# Sheet5.net
KiCad netlist of a schematic drawn in Altium Designer
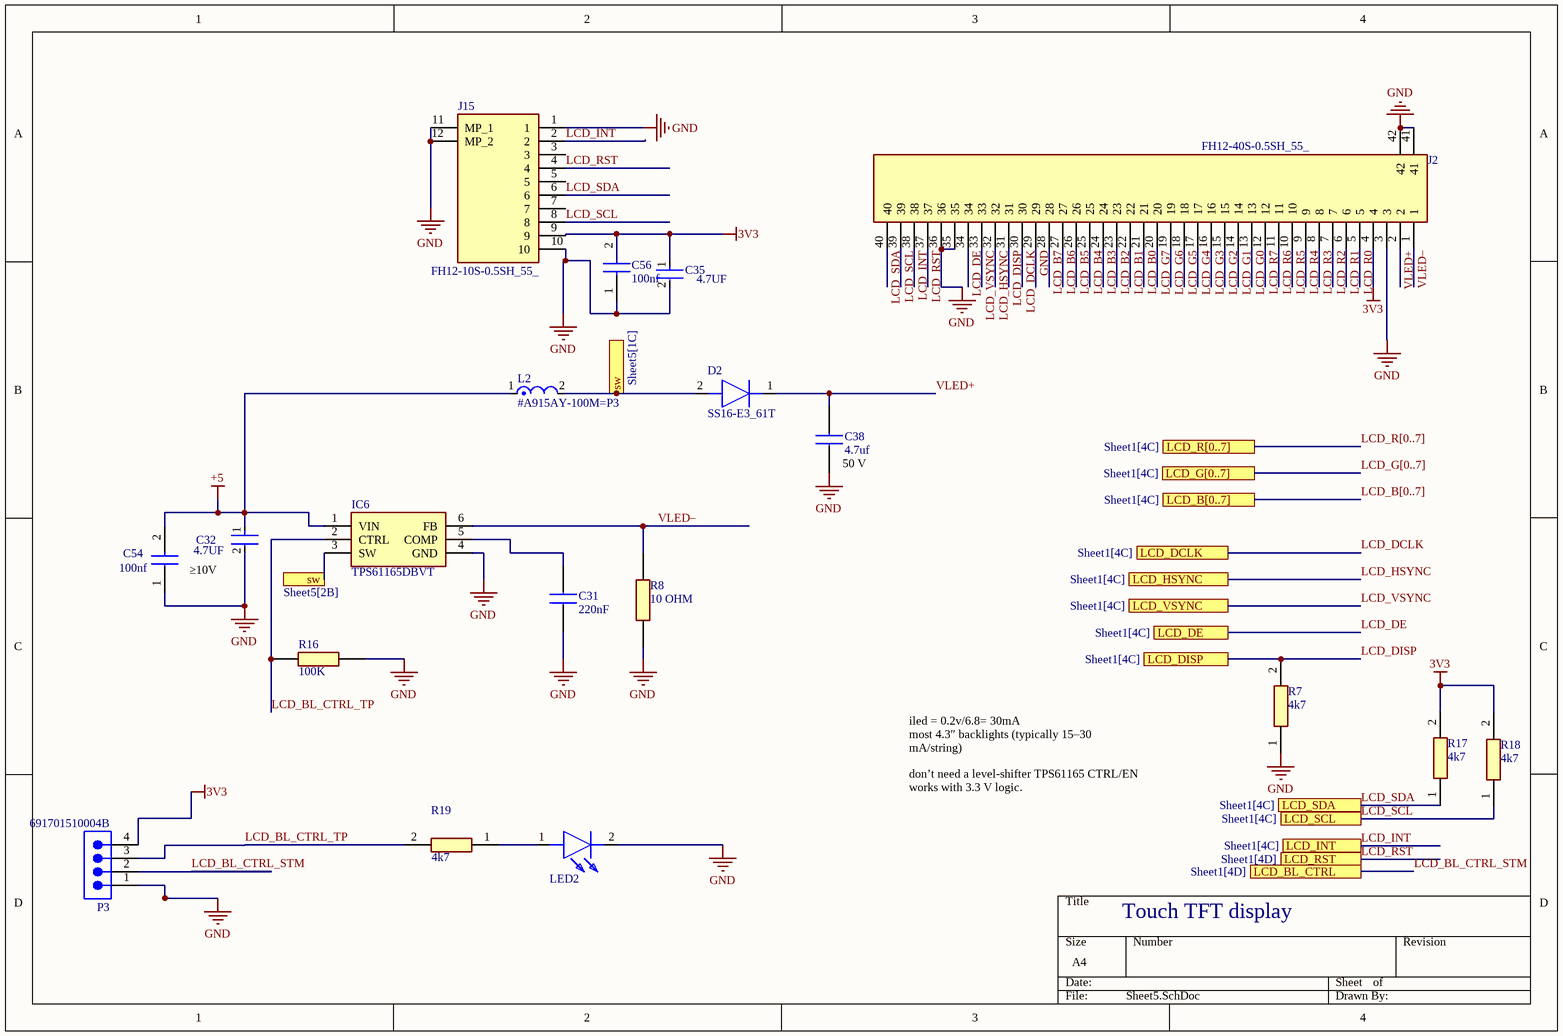
[diagram p0: Sheet5.SchDoc]

(export (version "E")
  (design (tool "Eeschema 10.0.6"))
  (components
    (comp (ref "C31")
      (value "220nF")
      (footprint "CAPC1608X87N")
      (description "WALSIN - 0603B223K500CT - CAPACITOR, MLCC, X7R, 0.022UF, 50V, 0603")
      (fields
        (field (name "MANUFACTURER_PART_NUMBER") "0603B223K500CT")
        (field (name "MOUSER PART NUMBER") "791-0603B223K500CT")
      )
      (libsource (lib "0603B223K500CT") (part "0603B223K500CT"))
    )
    (comp (ref "C32")
      (value "4.7UF")
      (footprint "FP-CL10-IPC_A")
      (description "Cap Ceramic 2.2uF 10V X7R ±10% Pad SMD 0603 +125°C T/R")
      (fields (field (name "TOLERANCE") "10%"))
      (libsource (lib "Altium Content Vault") (part "b4654b650e69147ec39a6b967a45e02"))
    )
    (comp (ref "C35")
      (value "4.7UF")
      (footprint "FP-CL10-IPC_A")
      (description "Cap Ceramic 2.2uF 10V X7R ±10% Pad SMD 0603 +125°C T/R")
      (fields (field (name "TOLERANCE") "10%"))
      (libsource (lib "Altium Content Vault") (part "b4654b650e69147ec39a6b967a45e02"))
    )
    (comp (ref "C38")
      (value "4.7uf")
      (footprint "CAPC1608X95N")
      (fields (field (name "MANUFACTURER_PART_NUMBER") "0603X105K250CT"))
      (libsource (lib "0603X105K250CT") (part "0603X105K250CT"))
    )
    (comp (ref "C54")
      (value "100nf")
      (footprint "SamacSys:CAPC1608X95N")
      (description "Capacitor")
      (fields (field (name "MANUFACTURER_PART_NUMBER") "VJ0603Y104KXACW1BC"))
      (libsource (lib "*") (part "VJ0603Y104KXACW1BC"))
    )
    (comp (ref "C56")
      (value "100nf")
      (footprint "SamacSys:CAPC1608X95N")
      (description "Capacitor")
      (fields (field (name "MANUFACTURER_PART_NUMBER") "VJ0603Y104KXACW1BC"))
      (libsource (lib "*") (part "VJ0603Y104KXACW1BC"))
    )
    (comp (ref "D2")
      (value "SS16-E3_61T")
      (footprint "SamacSys:DIOM5127X229N")
      (description "Diode")
      (fields
        (field (name "MANUFACTURER_PART_NUMBER") "SS16-E3/61T")
        (field (name "MOUSER PART NUMBER") "625-SS16-E3")
      )
      (libsource (lib "*") (part "SS16-E3_61T"))
    )
    (comp (ref "IC6")
      (value "TPS61165DBVT")
      (footprint "SamacSys:SOT95P280X145-6N")
      (description "Integrated Circuit")
      (fields (field (name "MOUSER PART NUMBER") "595-TPS61165DBVT"))
      (libsource (lib "*") (part "TPS61165DBVT"))
    )
    (comp (ref "J2")
      (value "FH12-40S-0.5SH_55_")
      (footprint "SamacSys:FH1240S05SH55")
      (description "Connector")
      (fields
        (field (name "MANUFACTURER_PART_NUMBER") "FH12-40S-0.5SH(55)")
        (field (name "MOUSER PART NUMBER") "798-FH12-40S-0.5SH55")
      )
      (libsource (lib "*") (part "FH12-40S-0.5SH_55_"))
    )
    (comp (ref "J15")
      (value "FH12-10S-0.5SH_55_")
      (footprint "SamacSys:FH1210S05SH55")
      (description "Connector")
      (fields
        (field (name "MANUFACTURER_PART_NUMBER") "FH12-10S-0.5SH(55)")
        (field (name "MOUSER PART NUMBER") "798-FH12-10S-0.5SH55")
      )
      (libsource (lib "*") (part "FH12-10S-0.5SH_55_"))
    )
    (comp (ref "L2")
      (value "#A915AY-100M=P3")
      (footprint "FP-D53LC-MFG")
      (description "FIXED IND 10UH 1.49A 90 MOHM SMD")
      (fields (field (name "TOLERANCE") "20%"))
      (libsource (lib "Altium Content Vault") (part "ae3b6ca10b736fc74204ce580bf9b8e"))
    )
    (comp (ref "LED2")
      (value "KPTL-3216SURCK-01-VS")
      (footprint "SamacSys:KPTL3216SURCK01VS")
      (description "LED")
      (libsource (lib "*") (part "KPTL-3216SURCK-01-VS"))
    )
    (comp (ref "P3")
      (value "691701510004B")
      (footprint "691701510004B")
      (description "Terminal Block, 5.08MM, Close Vertical Pcb Header, Thr Type, 4 Pins")
      (libsource (lib "Altium Content Vault") (part "TBL - 1R - 04P - Male"))
    )
    (comp (ref "R7")
      (value "4k7")
      (footprint "SamacSys:RESC1608X55N")
      (description "Resistor")
      (fields
        (field (name "MANUFACTURER_PART_NUMBER") "CRCW06034K70JNEAC")
        (field (name "MOUSER PART NUMBER") "71-CRCW06034K70JNEAC")
      )
      (libsource (lib "*") (part "CRCW06034K70JNEAC"))
    )
    (comp (ref "R8")
      (value "10 OHM")
      (footprint "RESC1608X50N")
      (description "AR03BTCX6R80")
      (fields
        (field (name "MANUFACTURER_PART_NUMBER") "RCA0603100KFKEA")
        (field (name "MOUSER PART NUMBER") "71-RCA0603100KFKEA")
      )
      (libsource (lib "RCA0603100KFKEA") (part "RCA0603100KFKEA"))
    )
    (comp (ref "R16")
      (value "100K")
      (footprint "RESC1608X50N")
      (fields
        (field (name "MANUFACTURER_PART_NUMBER") "RCA0603100KFKEA")
        (field (name "MOUSER PART NUMBER") "71-RCA0603100KFKEA")
      )
      (libsource (lib "") (part "RCA0603100KFKEA_1"))
    )
    (comp (ref "R17")
      (value "4k7")
      (footprint "SamacSys:RESC1608X55N")
      (description "Resistor")
      (fields
        (field (name "MANUFACTURER_PART_NUMBER") "CRCW06034K70JNEAC")
        (field (name "MOUSER PART NUMBER") "71-CRCW06034K70JNEAC")
      )
      (libsource (lib "*") (part "CRCW06034K70JNEAC"))
    )
    (comp (ref "R18")
      (value "4k7")
      (footprint "SamacSys:RESC1608X55N")
      (description "Resistor")
      (fields
        (field (name "MANUFACTURER_PART_NUMBER") "CRCW06034K70JNEAC")
        (field (name "MOUSER PART NUMBER") "71-CRCW06034K70JNEAC")
      )
      (libsource (lib "*") (part "CRCW06034K70JNEAC"))
    )
    (comp (ref "R19")
      (value "4k7")
      (footprint "SamacSys:RESC1608X55N")
      (description "Resistor")
      (fields
        (field (name "MANUFACTURER_PART_NUMBER") "CRCW06034K70JNEAC")
        (field (name "MOUSER PART NUMBER") "71-CRCW06034K70JNEAC")
      )
      (libsource (lib "") (part "CRCW06034K70JNEAC_1"))
    )
  )
  (nets
    (net (code "1") (name "+5") (class "Default")
      (node (ref "C32") (pin "1") (pinfunction "1_1") (pintype "passive"))
      (node (ref "C54") (pin "2") (pinfunction "2_2") (pintype "passive"))
      (node (ref "IC6") (pin "1") (pinfunction "VIN_1") (pintype "passive"))
      (node (ref "L2") (pin "1") (pinfunction "1_1") (pintype "passive"))
    )
    (net (code "2") (name "/LCD_B0") (class "Default")
      (node (ref "J2") (pin "21") (pinfunction "21_21") (pintype "passive"))
    )
    (net (code "3") (name "/LCD_B1") (class "Default")
      (node (ref "J2") (pin "22") (pinfunction "22_22") (pintype "passive"))
    )
    (net (code "4") (name "/LCD_B2") (class "Default")
      (node (ref "J2") (pin "23") (pinfunction "23_23") (pintype "passive"))
    )
    (net (code "5") (name "/LCD_B3") (class "Default")
      (node (ref "J2") (pin "24") (pinfunction "24_24") (pintype "passive"))
    )
    (net (code "6") (name "/LCD_B4") (class "Default")
      (node (ref "J2") (pin "25") (pinfunction "25_25") (pintype "passive"))
    )
    (net (code "7") (name "/LCD_B5") (class "Default")
      (node (ref "J2") (pin "26") (pinfunction "26_26") (pintype "passive"))
    )
    (net (code "8") (name "/LCD_B6") (class "Default")
      (node (ref "J2") (pin "27") (pinfunction "27_27") (pintype "passive"))
    )
    (net (code "9") (name "/LCD_B7") (class "Default")
      (node (ref "J2") (pin "28") (pinfunction "28_28") (pintype "passive"))
    )
    (net (code "10") (name "/LCD_BL_CTRL_STM") (class "Default")
      (node (ref "P3") (pin "2") (pinfunction "2_2") (pintype "passive"))
    )
    (net (code "11") (name "/LCD_BL_CTRL_TP") (class "Default")
      (node (ref "IC6") (pin "2") (pinfunction "CTRL_2") (pintype "passive"))
      (node (ref "P3") (pin "3") (pinfunction "3_3") (pintype "passive"))
      (node (ref "R16") (pin "1") (pinfunction "1_1") (pintype "passive"))
      (node (ref "R19") (pin "2") (pinfunction "2_2") (pintype "passive"))
    )
    (net (code "13") (name "/LCD_DCLK") (class "Default")
      (node (ref "J2") (pin "30") (pinfunction "30_30") (pintype "passive"))
    )
    (net (code "14") (name "/LCD_DE") (class "Default")
      (node (ref "J2") (pin "34") (pinfunction "34_34") (pintype "passive"))
    )
    (net (code "15") (name "/LCD_DISP") (class "Default")
      (node (ref "J2") (pin "31") (pinfunction "31_31") (pintype "passive"))
      (node (ref "R7") (pin "2") (pinfunction "2_2") (pintype "passive"))
    )
    (net (code "16") (name "/LCD_G0") (class "Default")
      (node (ref "J2") (pin "13") (pinfunction "13_13") (pintype "passive"))
    )
    (net (code "17") (name "/LCD_G1") (class "Default")
      (node (ref "J2") (pin "14") (pinfunction "14_14") (pintype "passive"))
    )
    (net (code "18") (name "/LCD_G2") (class "Default")
      (node (ref "J2") (pin "15") (pinfunction "15_15") (pintype "passive"))
    )
    (net (code "19") (name "/LCD_G3") (class "Default")
      (node (ref "J2") (pin "16") (pinfunction "16_16") (pintype "passive"))
    )
    (net (code "20") (name "/LCD_G4") (class "Default")
      (node (ref "J2") (pin "17") (pinfunction "17_17") (pintype "passive"))
    )
    (net (code "21") (name "/LCD_G5") (class "Default")
      (node (ref "J2") (pin "18") (pinfunction "18_18") (pintype "passive"))
    )
    (net (code "22") (name "/LCD_G6") (class "Default")
      (node (ref "J2") (pin "19") (pinfunction "19_19") (pintype "passive"))
    )
    (net (code "23") (name "/LCD_G7") (class "Default")
      (node (ref "J2") (pin "20") (pinfunction "20_20") (pintype "passive"))
    )
    (net (code "25") (name "/LCD_HSYNC") (class "Default")
      (node (ref "J2") (pin "32") (pinfunction "32_32") (pintype "passive"))
    )
    (net (code "26") (name "/LCD_INT") (class "Default")
      (node (ref "J15") (pin "2") (pinfunction "2_2") (pintype "passive"))
      (node (ref "J2") (pin "38") (pinfunction "38_38") (pintype "passive"))
    )
    (net (code "27") (name "/LCD_R0") (class "Default")
      (node (ref "J2") (pin "5") (pinfunction "5_5") (pintype "passive"))
    )
    (net (code "28") (name "/LCD_R1") (class "Default")
      (node (ref "J2") (pin "6") (pinfunction "6_6") (pintype "passive"))
    )
    (net (code "29") (name "/LCD_R2") (class "Default")
      (node (ref "J2") (pin "7") (pinfunction "7_7") (pintype "passive"))
    )
    (net (code "30") (name "/LCD_R3") (class "Default")
      (node (ref "J2") (pin "8") (pinfunction "8_8") (pintype "passive"))
    )
    (net (code "31") (name "/LCD_R4") (class "Default")
      (node (ref "J2") (pin "9") (pinfunction "9_9") (pintype "passive"))
    )
    (net (code "32") (name "/LCD_R5") (class "Default")
      (node (ref "J2") (pin "10") (pinfunction "10_10") (pintype "passive"))
    )
    (net (code "33") (name "/LCD_R6") (class "Default")
      (node (ref "J2") (pin "11") (pinfunction "11_11") (pintype "passive"))
    )
    (net (code "34") (name "/LCD_R7") (class "Default")
      (node (ref "J2") (pin "12") (pinfunction "12_12") (pintype "passive"))
    )
    (net (code "35") (name "/LCD_RST") (class "Default")
      (node (ref "J15") (pin "4") (pinfunction "4_4") (pintype "passive"))
      (node (ref "J2") (pin "37") (pinfunction "37_37") (pintype "passive"))
    )
    (net (code "37") (name "/LCD_SCL") (class "Default")
      (node (ref "J15") (pin "8") (pinfunction "8_8") (pintype "passive"))
      (node (ref "J2") (pin "39") (pinfunction "39_39") (pintype "passive"))
      (node (ref "R18") (pin "1") (pinfunction "1_1") (pintype "passive"))
    )
    (net (code "38") (name "/LCD_SDA") (class "Default")
      (node (ref "J15") (pin "6") (pinfunction "6_6") (pintype "passive"))
      (node (ref "J2") (pin "40") (pinfunction "40_40") (pintype "passive"))
      (node (ref "R17") (pin "1") (pinfunction "1_1") (pintype "passive"))
    )
    (net (code "39") (name "/LCD_VSYNC") (class "Default")
      (node (ref "J2") (pin "33") (pinfunction "33_33") (pintype "passive"))
    )
    (net (code "40") (name "/VLED+") (class "Default")
      (node (ref "C38") (pin "2") (pinfunction "2_2") (pintype "passive"))
      (node (ref "D2") (pin "1") (pinfunction "K_1") (pintype "passive"))
      (node (ref "J2") (pin "2") (pinfunction "2_2") (pintype "passive"))
    )
    (net (code "41") (name "/VLED–") (class "Default")
      (node (ref "IC6") (pin "6") (pinfunction "FB_6") (pintype "passive"))
      (node (ref "J2") (pin "1") (pinfunction "1_1") (pintype "passive"))
      (node (ref "R8") (pin "2") (pinfunction "2_2") (pintype "passive"))
    )
    (net (code "42") (name "/sw") (class "Default")
      (node (ref "D2") (pin "2") (pinfunction "A_2") (pintype "passive"))
      (node (ref "IC6") (pin "3") (pinfunction "SW_3") (pintype "passive"))
      (node (ref "L2") (pin "2") (pinfunction "2_2") (pintype "passive"))
    )
    (net (code "43") (name "3V3") (class "Default")
      (node (ref "C35") (pin "1") (pinfunction "1_1") (pintype "passive"))
      (node (ref "C56") (pin "2") (pinfunction "2_2") (pintype "passive"))
      (node (ref "J15") (pin "9") (pinfunction "9_9") (pintype "passive"))
      (node (ref "J2") (pin "4") (pinfunction "4_4") (pintype "passive"))
      (node (ref "P3") (pin "4") (pinfunction "4_4") (pintype "passive"))
      (node (ref "R17") (pin "2") (pinfunction "2_2") (pintype "passive"))
      (node (ref "R18") (pin "2") (pinfunction "2_2") (pintype "passive"))
    )
    (net (code "44") (name "GND") (class "Default")
      (node (ref "C31") (pin "1") (pinfunction "1_1") (pintype "passive"))
      (node (ref "C32") (pin "2") (pinfunction "2_2") (pintype "passive"))
      (node (ref "C35") (pin "2") (pinfunction "2_2") (pintype "passive"))
      (node (ref "C38") (pin "1") (pinfunction "1_1") (pintype "passive"))
      (node (ref "C54") (pin "1") (pinfunction "1_1") (pintype "passive"))
      (node (ref "C56") (pin "1") (pinfunction "1_1") (pintype "passive"))
      (node (ref "IC6") (pin "4") (pinfunction "GND_4") (pintype "passive"))
      (node (ref "J15") (pin "1") (pinfunction "1_1") (pintype "passive"))
      (node (ref "J15") (pin "10") (pinfunction "10_10") (pintype "passive"))
      (node (ref "J15") (pin "11") (pinfunction "MP_1_11") (pintype "passive"))
      (node (ref "J15") (pin "12") (pinfunction "MP_2_12") (pintype "passive"))
      (node (ref "J2") (pin "29") (pinfunction "29_29") (pintype "passive"))
      (node (ref "J2") (pin "3") (pinfunction "3_3") (pintype "passive"))
      (node (ref "J2") (pin "35") (pinfunction "35_35") (pintype "passive"))
      (node (ref "J2") (pin "36") (pinfunction "36_36") (pintype "passive"))
      (node (ref "J2") (pin "41") (pinfunction "41_41") (pintype "passive"))
      (node (ref "J2") (pin "42") (pinfunction "42_42") (pintype "passive"))
      (node (ref "LED2") (pin "2") (pinfunction "K_2") (pintype "passive"))
      (node (ref "P3") (pin "1") (pinfunction "1_1") (pintype "passive"))
      (node (ref "R16") (pin "2") (pinfunction "2_2") (pintype "passive"))
      (node (ref "R7") (pin "1") (pinfunction "1_1") (pintype "passive"))
      (node (ref "R8") (pin "1") (pinfunction "1_1") (pintype "passive"))
    )
    (net (code "45") (name "Net-(IC6-COMP)") (class "Default")
      (node (ref "C31") (pin "2") (pinfunction "2_2") (pintype "passive"))
      (node (ref "IC6") (pin "5") (pinfunction "COMP_5") (pintype "passive"))
    )
    (net (code "46") (name "Net-(LED2-A)") (class "Default")
      (node (ref "LED2") (pin "1") (pinfunction "A_1") (pintype "passive"))
      (node (ref "R19") (pin "1") (pinfunction "1_1") (pintype "passive"))
    )
    (net (code "47") (name "unconnected-(J15-Pad3)") (class "Default")
      (node (ref "J15") (pin "3") (pinfunction "3_3") (pintype "passive"))
    )
    (net (code "48") (name "unconnected-(J15-Pad5)") (class "Default")
      (node (ref "J15") (pin "5") (pinfunction "5_5") (pintype "passive"))
    )
    (net (code "49") (name "unconnected-(J15-Pad7)") (class "Default")
      (node (ref "J15") (pin "7") (pinfunction "7_7") (pintype "passive"))
    )
  )
)
